# FINGER_MCU.net
KiCad netlist of a schematic drawn in Altium Designer
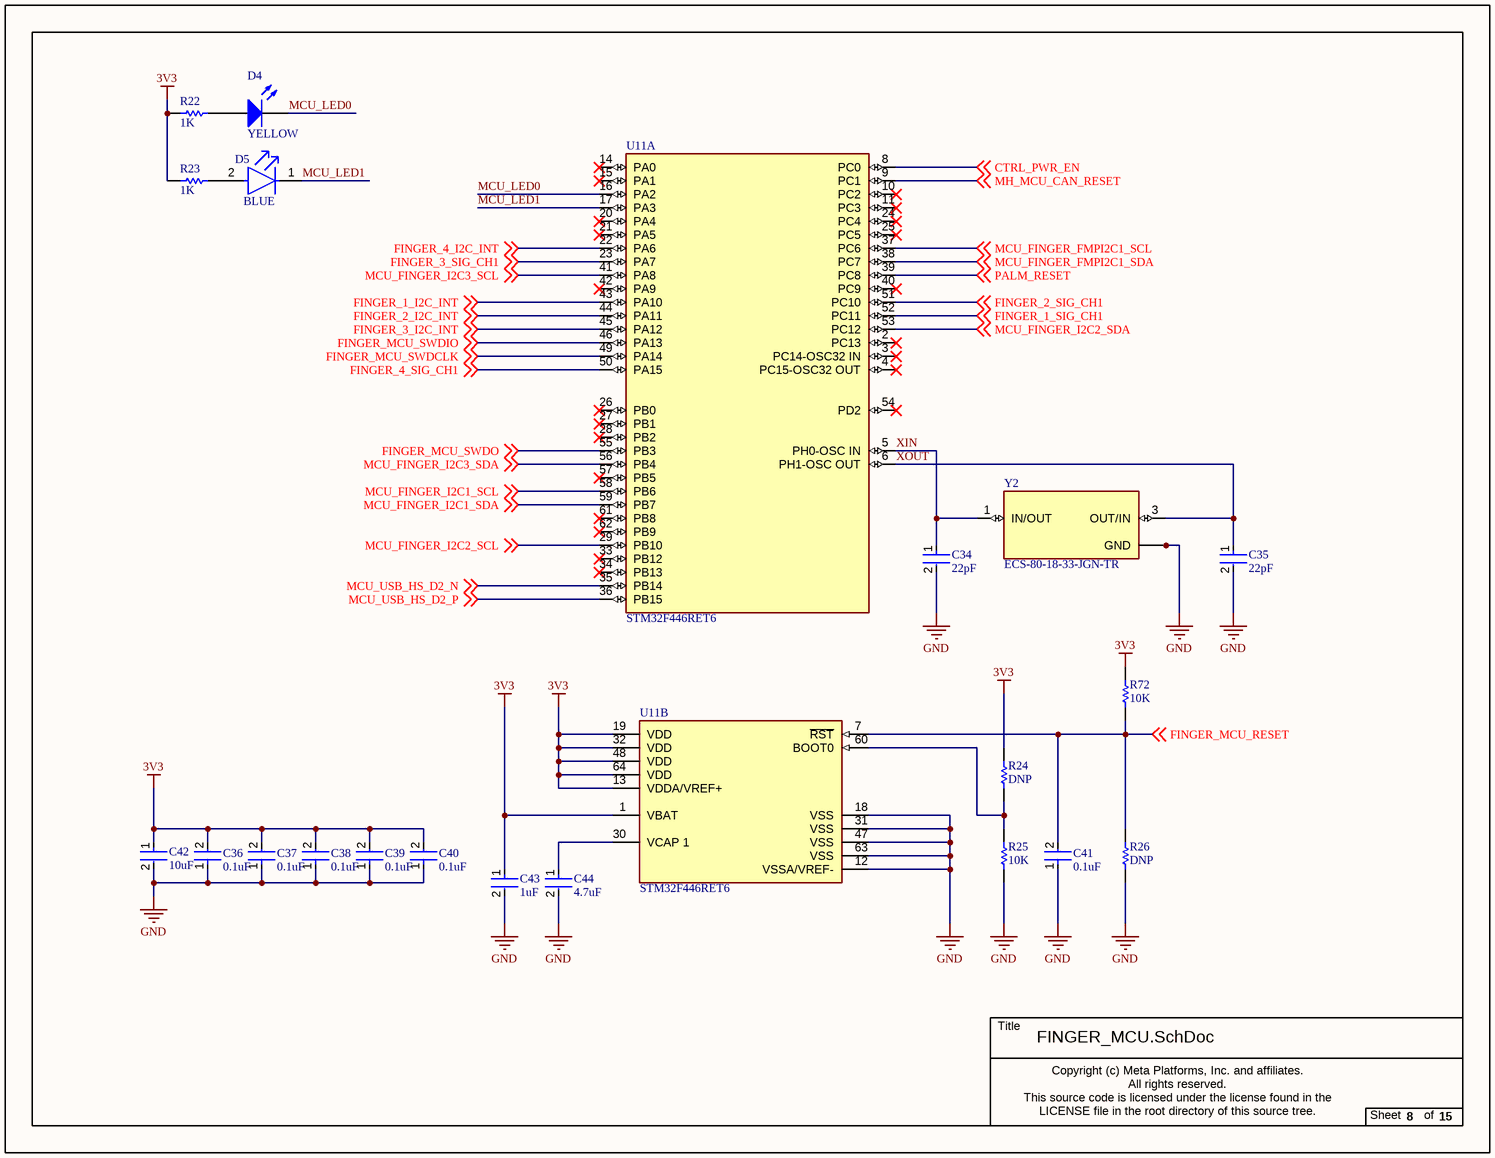
[diagram p0: FINGER_MCU.SchDoc]

(export (version "E")
  (design (tool "Eeschema 10.0.6"))
  (components
    (comp (ref "C34")
      (value "22pF")
      (footprint "FP-0402-L_1_0_1-W_0_5_0_1-MFG")
      (description "General Purpose Ceramic Capacitor, 0402, 22pF, 5%, C0G, 30ppm/°C, 50V")
      (fields (field (name "VOLTAGE") "50V") (field (name "TOLERANCE") "5%"))
      (libsource (lib "Altium Content Vault") (part "b4654b650e69147ec39a6b967a45e02"))
    )
    (comp (ref "C35")
      (value "22pF")
      (footprint "FP-0402-L_1_0_1-W_0_5_0_1-MFG")
      (description "General Purpose Ceramic Capacitor, 0402, 22pF, 5%, C0G, 30ppm/°C, 50V")
      (fields (field (name "VOLTAGE") "50V") (field (name "TOLERANCE") "5%"))
      (libsource (lib "Altium Content Vault") (part "b4654b650e69147ec39a6b967a45e02"))
    )
    (comp (ref "C36")
      (value "0.1uF")
      (footprint "FP-CC0201-BA-MFG")
      (description "CAP CER 0.1UF 6.3V X5R 0201")
      (fields (field (name "MANUFACTURER") "Yageo") (field (name "TOLERANCE") "0.1"))
      (libsource (lib "Altium Content Vault") (part "11868f565c42a9108669ba33697ecf6"))
    )
    (comp (ref "C37")
      (value "0.1uF")
      (footprint "FP-CC0201-BA-MFG")
      (description "CAP CER 0.1UF 6.3V X5R 0201")
      (fields (field (name "MANUFACTURER") "Yageo") (field (name "TOLERANCE") "0.1"))
      (libsource (lib "Altium Content Vault") (part "11868f565c42a9108669ba33697ecf6"))
    )
    (comp (ref "C38")
      (value "0.1uF")
      (footprint "FP-CC0201-BA-MFG")
      (description "CAP CER 0.1UF 6.3V X5R 0201")
      (fields (field (name "MANUFACTURER") "Yageo") (field (name "TOLERANCE") "0.1"))
      (libsource (lib "Altium Content Vault") (part "11868f565c42a9108669ba33697ecf6"))
    )
    (comp (ref "C39")
      (value "0.1uF")
      (footprint "FP-CC0201-BA-MFG")
      (description "CAP CER 0.1UF 6.3V X5R 0201")
      (fields (field (name "MANUFACTURER") "Yageo") (field (name "TOLERANCE") "0.1"))
      (libsource (lib "Altium Content Vault") (part "11868f565c42a9108669ba33697ecf6"))
    )
    (comp (ref "C40")
      (value "0.1uF")
      (footprint "FP-CC0201-BA-MFG")
      (description "CAP CER 0.1UF 6.3V X5R 0201")
      (fields (field (name "MANUFACTURER") "Yageo") (field (name "TOLERANCE") "0.1"))
      (libsource (lib "Altium Content Vault") (part "11868f565c42a9108669ba33697ecf6"))
    )
    (comp (ref "C41")
      (value "0.1uF")
      (footprint "FP-CC0201-BA-MFG")
      (description "CAP CER 0.1UF 6.3V X5R 0201")
      (fields (field (name "MANUFACTURER") "Yageo") (field (name "TOLERANCE") "0.1"))
      (libsource (lib "Altium Content Vault") (part "11868f565c42a9108669ba33697ecf6"))
    )
    (comp (ref "C42")
      (value "10uF")
      (footprint "FP-CL05A106MP5NUNC-MFG")
      (description "CAP CER 10UF 10V X5R 0402")
      (fields
        (field (name "OCTOPART") "https://octopart.com/cl05a106mp5nunc-samsung-22457395")
        (field (name "TOLERANCE") "20%")
      )
      (libsource (lib "Altium Content Vault") (part "b4654b650e69147ec39a6b967a45e02"))
    )
    (comp (ref "C43")
      (value "1uF")
      (footprint "FP-CL511-IPC_C")
      (description "Cap Ceramic 1uF 10V X5R ±10% SMD 0402 +85°C Paper T/R")
      (fields (field (name "TOLERANCE") "10%"))
      (libsource (lib "Altium Content Vault") (part "b4654b650e69147ec39a6b967a45e02"))
    )
    (comp (ref "C44")
      (value "4.7uF")
      (footprint "FP-C1005-050-0_15-MFG")
      (description "CAP CER 4.7UF 10V X5R 0402")
      (fields (field (name "TOLERANCE") "10%"))
      (libsource (lib "Altium Content Vault") (part "b4654b650e69147ec39a6b967a45e02"))
    )
    (comp (ref "D4")
      (value "YELLOW")
      (footprint "0603_A")
      (description "SMD mono-color Chip LED, WL-SMCW, Yellow")
      (fields (field (name "PARTNUMBER") "150060YS75000") (field (name "MANUFACTURER") "Wuerth Elektronik"))
      (libsource (lib "Altium Content Vault") (part "WE-LED_K1A2-2"))
    )
    (comp (ref "D5")
      (value "BLUE")
      (footprint "FP-LTST-C191TBKT-MFG")
      (description "LED BLUE CLEAR CHIP SMD")
      (libsource (lib "Altium Content Vault") (part "8706943c75ba83719d021d2fdc84c58"))
    )
    (comp (ref "R22")
      (value "1K")
      (footprint "RESC1005X40X25NL05T05")
      (description "Chip Resistor, 1 KOhm, +/- 1%, 100 mW, -55 to 155 degC, 0402 (1005 Metric), RoHS, Tape and Reel")
      (fields (field (name "PARTNUMBER") "ERJ-2RKF1001X") (field (name "MANUFACTURER") "Basic Passives"))
      (libsource (lib "Altium Content Vault") (part "RES-2"))
    )
    (comp (ref "R23")
      (value "1K")
      (footprint "RESC1005X40X25NL05T05")
      (description "Chip Resistor, 1 KOhm, +/- 1%, 100 mW, -55 to 155 degC, 0402 (1005 Metric), RoHS, Tape and Reel")
      (fields (field (name "PARTNUMBER") "ERJ-2RKF1001X") (field (name "MANUFACTURER") "Basic Passives"))
      (libsource (lib "Altium Content Vault") (part "RES-2"))
    )
    (comp (ref "R24")
      (value "DNP")
      (footprint "RESC1005X40X25ML05T10")
      (fields (field (name "PART NUMBER") "CRCW040210K0FKEDHP") (field (name "MANUFACTURER") "Vishay Dale"))
      (libsource (lib "Altium Content Vault") (part "RES"))
    )
    (comp (ref "R25")
      (value "10K")
      (footprint "RESC1005X40X25ML05T10")
      (fields (field (name "PART NUMBER") "CRCW040210K0FKEDHP") (field (name "MANUFACTURER") "Vishay Dale"))
      (libsource (lib "Altium Content Vault") (part "RES"))
    )
    (comp (ref "R26")
      (value "DNP")
      (footprint "RESC1005X40X25NL05T10")
      (fields (field (name "MANUFACTURER") "Yageo / Phycomp") (field (name "PART NUMBER") "RC0402JR-070RL"))
      (libsource (lib "Altium Content Vault") (part "RES"))
    )
    (comp (ref "R72")
      (value "10K")
      (footprint "RESC1005X40X25ML05T10")
      (fields (field (name "PART NUMBER") "CRCW040210K0FKEDHP") (field (name "MANUFACTURER") "Vishay Dale"))
      (libsource (lib "Altium Content Vault") (part "RES"))
    )
    (comp (ref "U11")
      (value "STM32F446RET6")
      (footprint "FP-LQFP64-5W-MFG")
      (description "IC MCU 32BIT 512KB FLASH 64LQFP")
      (fields
        (field (name "OCTOPART") "https://octopart.com/stm32f446ret6-stmicroelectronics-52642920")
        (field (name "MANUFACTURER") "ST")
      )
      (libsource (lib "Altium Content Vault") (part "ee11adc32c0ab33b933cccf4348c338"))
    )
    (comp (ref "Y2")
      (value "ECS-80-18-33-JGN-TR")
      (footprint "ECS-80-18-33-JGN-TR:XTAL_ECS-240-8-33-AGN-TR")
      (fields (field (name "MF") "{'manufacturer': u'ECS Inc.'}"))
      (libsource (lib "*") (part "ECS-80-18-33-JGN-TR"))
    )
  )
  (nets
    (net (code "1") (name "/MCU_LED0") (class "Default")
      (node (ref "D4") (pin "1") (pinfunction "K_1") (pintype "passive"))
      (node (ref "U11") (pin "16") (pinfunction "PA2_16") (pintype "bidirectional"))
    )
    (net (code "2") (name "/MCU_LED1") (class "Default")
      (node (ref "D5") (pin "1") (pinfunction "C_1") (pintype "passive"))
      (node (ref "U11") (pin "17") (pinfunction "PA3_17") (pintype "bidirectional"))
    )
    (net (code "3") (name "/XIN") (class "Default")
      (node (ref "C34") (pin "1") (pinfunction "1_1") (pintype "passive"))
      (node (ref "U11") (pin "5") (pinfunction "PH0-OSC_IN_5") (pintype "bidirectional"))
      (node (ref "Y2") (pin "1") (pinfunction "IN/OUT_1") (pintype "bidirectional"))
    )
    (net (code "4") (name "/XOUT") (class "Default")
      (node (ref "C35") (pin "1") (pinfunction "1_1") (pintype "passive"))
      (node (ref "U11") (pin "6") (pinfunction "PH1-OSC_OUT_6") (pintype "bidirectional"))
      (node (ref "Y2") (pin "3") (pinfunction "OUT/IN_3") (pintype "bidirectional"))
    )
    (net (code "5") (name "3V3") (class "Default")
      (node (ref "C36") (pin "2") (pinfunction "2_2") (pintype "passive"))
      (node (ref "C37") (pin "2") (pinfunction "2_2") (pintype "passive"))
      (node (ref "C38") (pin "2") (pinfunction "2_2") (pintype "passive"))
      (node (ref "C39") (pin "2") (pinfunction "2_2") (pintype "passive"))
      (node (ref "C40") (pin "2") (pinfunction "2_2") (pintype "passive"))
      (node (ref "C42") (pin "1") (pinfunction "1_1") (pintype "passive"))
      (node (ref "C43") (pin "1") (pinfunction "1_1") (pintype "passive"))
      (node (ref "R22") (pin "1") (pinfunction "1_1") (pintype "passive"))
      (node (ref "R23") (pin "1") (pinfunction "1_1") (pintype "passive"))
      (node (ref "R24") (pin "2") (pinfunction "2_2") (pintype "passive"))
      (node (ref "R72") (pin "2") (pinfunction "2_2") (pintype "passive"))
      (node (ref "U11") (pin "1") (pinfunction "VBAT_1") (pintype "power_in"))
      (node (ref "U11") (pin "13") (pinfunction "VDDA/VREF+_13") (pintype "power_in"))
      (node (ref "U11") (pin "19") (pinfunction "VDD_19") (pintype "power_in"))
      (node (ref "U11") (pin "32") (pinfunction "VDD_32") (pintype "power_in"))
      (node (ref "U11") (pin "48") (pinfunction "VDD_48") (pintype "power_in"))
      (node (ref "U11") (pin "64") (pinfunction "VDD_64") (pintype "power_in"))
    )
    (net (code "6") (name "CTRL_PWR_EN") (class "Default")
      (node (ref "U11") (pin "8") (pinfunction "PC0_8") (pintype "bidirectional"))
    )
    (net (code "7") (name "FINGER_1_I2C_INT") (class "Default")
      (node (ref "U11") (pin "43") (pinfunction "PA10_43") (pintype "bidirectional"))
    )
    (net (code "8") (name "FINGER_1_SIG_CH1") (class "Default")
      (node (ref "U11") (pin "52") (pinfunction "PC11_52") (pintype "bidirectional"))
    )
    (net (code "9") (name "FINGER_2_I2C_INT") (class "Default")
      (node (ref "U11") (pin "44") (pinfunction "PA11_44") (pintype "bidirectional"))
    )
    (net (code "10") (name "FINGER_2_SIG_CH1") (class "Default")
      (node (ref "U11") (pin "51") (pinfunction "PC10_51") (pintype "bidirectional"))
    )
    (net (code "11") (name "FINGER_3_I2C_INT") (class "Default")
      (node (ref "U11") (pin "45") (pinfunction "PA12_45") (pintype "bidirectional"))
    )
    (net (code "12") (name "FINGER_3_SIG_CH1") (class "Default")
      (node (ref "U11") (pin "23") (pinfunction "PA7_23") (pintype "bidirectional"))
    )
    (net (code "13") (name "FINGER_4_I2C_INT") (class "Default")
      (node (ref "U11") (pin "22") (pinfunction "PA6_22") (pintype "bidirectional"))
    )
    (net (code "14") (name "FINGER_4_SIG_CH1") (class "Default")
      (node (ref "U11") (pin "50") (pinfunction "PA15_50") (pintype "bidirectional"))
    )
    (net (code "15") (name "FINGER_MCU_RESET") (class "Default")
      (node (ref "C41") (pin "2") (pinfunction "2_2") (pintype "passive"))
      (node (ref "R26") (pin "2") (pinfunction "2_2") (pintype "passive"))
      (node (ref "R72") (pin "1") (pinfunction "1_1") (pintype "passive"))
      (node (ref "U11") (pin "7") (pinfunction "~{RST}_7") (pintype "input"))
    )
    (net (code "16") (name "FINGER_MCU_SWDCLK") (class "Default")
      (node (ref "U11") (pin "49") (pinfunction "PA14_49") (pintype "bidirectional"))
    )
    (net (code "17") (name "FINGER_MCU_SWDIO") (class "Default")
      (node (ref "U11") (pin "46") (pinfunction "PA13_46") (pintype "bidirectional"))
    )
    (net (code "18") (name "FINGER_MCU_SWDO") (class "Default")
      (node (ref "U11") (pin "55") (pinfunction "PB3_55") (pintype "bidirectional"))
    )
    (net (code "19") (name "GND") (class "Default")
      (node (ref "C34") (pin "2") (pinfunction "2_2") (pintype "passive"))
      (node (ref "C35") (pin "2") (pinfunction "2_2") (pintype "passive"))
      (node (ref "C36") (pin "1") (pinfunction "1_1") (pintype "passive"))
      (node (ref "C37") (pin "1") (pinfunction "1_1") (pintype "passive"))
      (node (ref "C38") (pin "1") (pinfunction "1_1") (pintype "passive"))
      (node (ref "C39") (pin "1") (pinfunction "1_1") (pintype "passive"))
      (node (ref "C40") (pin "1") (pinfunction "1_1") (pintype "passive"))
      (node (ref "C41") (pin "1") (pinfunction "1_1") (pintype "passive"))
      (node (ref "C42") (pin "2") (pinfunction "2_2") (pintype "passive"))
      (node (ref "C43") (pin "2") (pinfunction "2_2") (pintype "passive"))
      (node (ref "C44") (pin "2") (pinfunction "2_2") (pintype "passive"))
      (node (ref "R25") (pin "1") (pinfunction "1_1") (pintype "passive"))
      (node (ref "R26") (pin "1") (pinfunction "1_1") (pintype "passive"))
      (node (ref "U11") (pin "12") (pinfunction "VSSA/VREF-_12") (pintype "power_in"))
      (node (ref "U11") (pin "18") (pinfunction "VSS_18") (pintype "power_in"))
      (node (ref "U11") (pin "31") (pinfunction "VSS_31") (pintype "power_in"))
      (node (ref "U11") (pin "47") (pinfunction "VSS_47") (pintype "power_in"))
      (node (ref "U11") (pin "63") (pinfunction "VSS_63") (pintype "power_in"))
      (node (ref "Y2") (pin "2") (pinfunction "GND_2") (pintype "power_in"))
      (node (ref "Y2") (pin "4") (pinfunction "GND_4") (pintype "power_in"))
    )
    (net (code "20") (name "MCU_FINGER_FMPI2C1_SCL") (class "Default")
      (node (ref "U11") (pin "37") (pinfunction "PC6_37") (pintype "bidirectional"))
    )
    (net (code "21") (name "MCU_FINGER_FMPI2C1_SDA") (class "Default")
      (node (ref "U11") (pin "38") (pinfunction "PC7_38") (pintype "bidirectional"))
    )
    (net (code "22") (name "MCU_FINGER_I2C1_SCL") (class "Default")
      (node (ref "U11") (pin "58") (pinfunction "PB6_58") (pintype "bidirectional"))
    )
    (net (code "23") (name "MCU_FINGER_I2C1_SDA") (class "Default")
      (node (ref "U11") (pin "59") (pinfunction "PB7_59") (pintype "bidirectional"))
    )
    (net (code "24") (name "MCU_FINGER_I2C2_SCL") (class "Default")
      (node (ref "U11") (pin "29") (pinfunction "PB10_29") (pintype "bidirectional"))
    )
    (net (code "25") (name "MCU_FINGER_I2C2_SDA") (class "Default")
      (node (ref "U11") (pin "53") (pinfunction "PC12_53") (pintype "bidirectional"))
    )
    (net (code "26") (name "MCU_FINGER_I2C3_SCL") (class "Default")
      (node (ref "U11") (pin "41") (pinfunction "PA8_41") (pintype "bidirectional"))
    )
    (net (code "27") (name "MCU_FINGER_I2C3_SDA") (class "Default")
      (node (ref "U11") (pin "56") (pinfunction "PB4_56") (pintype "bidirectional"))
    )
    (net (code "28") (name "MCU_USB_HS_D2_N") (class "Default")
      (node (ref "U11") (pin "35") (pinfunction "PB14_35") (pintype "bidirectional"))
    )
    (net (code "29") (name "MCU_USB_HS_D2_P") (class "Default")
      (node (ref "U11") (pin "36") (pinfunction "PB15_36") (pintype "bidirectional"))
    )
    (net (code "30") (name "MH_MCU_CAN_RESET") (class "Default")
      (node (ref "U11") (pin "9") (pinfunction "PC1_9") (pintype "bidirectional"))
    )
    (net (code "31") (name "Net-(D4-A)") (class "Default")
      (node (ref "D4") (pin "2") (pinfunction "A_2") (pintype "passive"))
      (node (ref "R22") (pin "2") (pinfunction "2_2") (pintype "passive"))
    )
    (net (code "32") (name "Net-(D5-A)") (class "Default")
      (node (ref "D5") (pin "2") (pinfunction "A_2") (pintype "passive"))
      (node (ref "R23") (pin "2") (pinfunction "2_2") (pintype "passive"))
    )
    (net (code "33") (name "Net-(U11B-BOOT0)") (class "Default")
      (node (ref "R24") (pin "1") (pinfunction "1_1") (pintype "passive"))
      (node (ref "R25") (pin "2") (pinfunction "2_2") (pintype "passive"))
      (node (ref "U11") (pin "60") (pinfunction "BOOT0_60") (pintype "input"))
    )
    (net (code "34") (name "Net-(U11B-VCAP_1)") (class "Default")
      (node (ref "C44") (pin "1") (pinfunction "1_1") (pintype "passive"))
      (node (ref "U11") (pin "30") (pinfunction "VCAP_1_30") (pintype "power_in"))
    )
    (net (code "35") (name "PALM_RESET") (class "Default")
      (node (ref "U11") (pin "39") (pinfunction "PC8_39") (pintype "bidirectional"))
    )
    (net (code "36") (name "unconnected-(U11A-PA0-Pad14)") (class "Default")
      (node (ref "U11") (pin "14") (pinfunction "PA0_14") (pintype "bidirectional+no_connect"))
    )
    (net (code "37") (name "unconnected-(U11A-PA1-Pad15)") (class "Default")
      (node (ref "U11") (pin "15") (pinfunction "PA1_15") (pintype "bidirectional+no_connect"))
    )
    (net (code "38") (name "unconnected-(U11A-PA4-Pad20)") (class "Default")
      (node (ref "U11") (pin "20") (pinfunction "PA4_20") (pintype "bidirectional+no_connect"))
    )
    (net (code "39") (name "unconnected-(U11A-PA5-Pad21)") (class "Default")
      (node (ref "U11") (pin "21") (pinfunction "PA5_21") (pintype "bidirectional+no_connect"))
    )
    (net (code "40") (name "unconnected-(U11A-PA9-Pad42)") (class "Default")
      (node (ref "U11") (pin "42") (pinfunction "PA9_42") (pintype "bidirectional+no_connect"))
    )
    (net (code "41") (name "unconnected-(U11A-PB0-Pad26)") (class "Default")
      (node (ref "U11") (pin "26") (pinfunction "PB0_26") (pintype "bidirectional+no_connect"))
    )
    (net (code "42") (name "unconnected-(U11A-PB1-Pad27)") (class "Default")
      (node (ref "U11") (pin "27") (pinfunction "PB1_27") (pintype "bidirectional+no_connect"))
    )
    (net (code "43") (name "unconnected-(U11A-PB2-Pad28)") (class "Default")
      (node (ref "U11") (pin "28") (pinfunction "PB2_28") (pintype "bidirectional+no_connect"))
    )
    (net (code "44") (name "unconnected-(U11A-PB5-Pad57)") (class "Default")
      (node (ref "U11") (pin "57") (pinfunction "PB5_57") (pintype "bidirectional+no_connect"))
    )
    (net (code "45") (name "unconnected-(U11A-PB8-Pad61)") (class "Default")
      (node (ref "U11") (pin "61") (pinfunction "PB8_61") (pintype "bidirectional+no_connect"))
    )
    (net (code "46") (name "unconnected-(U11A-PB9-Pad62)") (class "Default")
      (node (ref "U11") (pin "62") (pinfunction "PB9_62") (pintype "bidirectional+no_connect"))
    )
    (net (code "47") (name "unconnected-(U11A-PB12-Pad33)") (class "Default")
      (node (ref "U11") (pin "33") (pinfunction "PB12_33") (pintype "bidirectional+no_connect"))
    )
    (net (code "48") (name "unconnected-(U11A-PB13-Pad34)") (class "Default")
      (node (ref "U11") (pin "34") (pinfunction "PB13_34") (pintype "bidirectional+no_connect"))
    )
    (net (code "49") (name "unconnected-(U11A-PC2-Pad10)") (class "Default")
      (node (ref "U11") (pin "10") (pinfunction "PC2_10") (pintype "bidirectional+no_connect"))
    )
    (net (code "50") (name "unconnected-(U11A-PC3-Pad11)") (class "Default")
      (node (ref "U11") (pin "11") (pinfunction "PC3_11") (pintype "bidirectional+no_connect"))
    )
    (net (code "51") (name "unconnected-(U11A-PC4-Pad24)") (class "Default")
      (node (ref "U11") (pin "24") (pinfunction "PC4_24") (pintype "bidirectional+no_connect"))
    )
    (net (code "52") (name "unconnected-(U11A-PC5-Pad25)") (class "Default")
      (node (ref "U11") (pin "25") (pinfunction "PC5_25") (pintype "bidirectional+no_connect"))
    )
    (net (code "53") (name "unconnected-(U11A-PC9-Pad40)") (class "Default")
      (node (ref "U11") (pin "40") (pinfunction "PC9_40") (pintype "bidirectional+no_connect"))
    )
    (net (code "54") (name "unconnected-(U11A-PC13-Pad2)") (class "Default")
      (node (ref "U11") (pin "2") (pinfunction "PC13_2") (pintype "bidirectional+no_connect"))
    )
    (net (code "55") (name "unconnected-(U11A-PC14-OSC32_IN-Pad3)") (class "Default")
      (node (ref "U11") (pin "3") (pinfunction "PC14-OSC32_IN_3") (pintype "bidirectional+no_connect"))
    )
    (net (code "56") (name "unconnected-(U11A-PC15-OSC32_OUT-Pad4)") (class "Default")
      (node (ref "U11") (pin "4") (pinfunction "PC15-OSC32_OUT_4") (pintype "bidirectional+no_connect"))
    )
    (net (code "57") (name "unconnected-(U11A-PD2-Pad54)") (class "Default")
      (node (ref "U11") (pin "54") (pinfunction "PD2_54") (pintype "bidirectional+no_connect"))
    )
  )
)
